# Bunza-DCC-Front-End.net
KiCad netlist of a schematic drawn in EAGLE
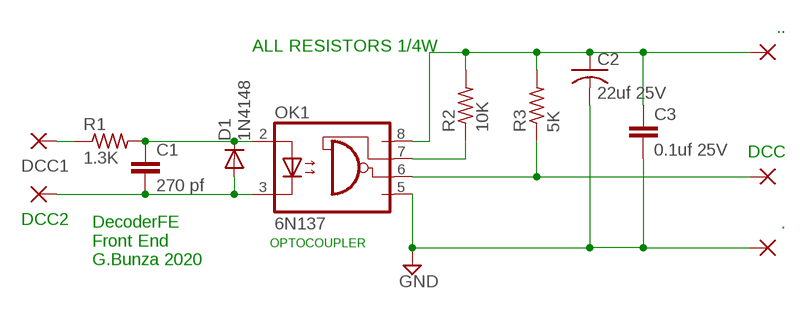
[diagram p0: schematic, sheet 1]

(export (version "E")
  (design (tool "Eeschema 10.0.6"))
  (components
    (comp (ref ".")
      (value "2,15/1,0")
      (footprint "eagle-import:2,15_1,0")
      (libsource (lib "eagle-import") (part "2,15/1,0"))
    )
    (comp (ref "..")
      (value "2,15/1,0")
      (footprint "eagle-import:2,15_1,0")
      (libsource (lib "eagle-import") (part "2,15/1,0"))
    )
    (comp (ref "C1")
      (value "270 pf")
      (footprint "eagle-import:AXIAL-5MM")
      (libsource (lib "eagle-import") (part "CAP_"))
    )
    (comp (ref "C2")
      (value "22uf 25V")
      (footprint "eagle-import:C050-035X075")
      (libsource (lib "eagle-import") (part "C-US050-035X075"))
    )
    (comp (ref "C3")
      (value "0.1uf 25V")
      (footprint "eagle-import:AXIAL-5MM")
      (libsource (lib "eagle-import") (part "CAP_"))
    )
    (comp (ref "D1")
      (value "1N4148")
      (footprint "eagle-import:DO35-7")
      (libsource (lib "eagle-import") (part "1N4148DO35-7"))
    )
    (comp (ref "DCC")
      (value "2,15/1,0")
      (footprint "eagle-import:2,15_1,0")
      (libsource (lib "eagle-import") (part "2,15/1,0"))
    )
    (comp (ref "DCC1")
      (value "2,15/1,0")
      (footprint "eagle-import:2,15_1,0")
      (libsource (lib "eagle-import") (part "2,15/1,0"))
    )
    (comp (ref "DCC2")
      (value "2,15/1,0")
      (footprint "eagle-import:2,15_1,0")
      (libsource (lib "eagle-import") (part "2,15/1,0"))
    )
    (comp (ref "OK1")
      (value "6N137")
      (footprint "eagle-import:DIL08")
      (libsource (lib "eagle-import") (part "6N137"))
    )
    (comp (ref "R1")
      (value "1.3K")
      (footprint "eagle-import:0204_7")
      (libsource (lib "eagle-import") (part "R-US_0204/7"))
    )
    (comp (ref "R2")
      (value "10K")
      (footprint "eagle-import:0204_7")
      (libsource (lib "eagle-import") (part "R-US_0204/7"))
    )
    (comp (ref "R3")
      (value "5K")
      (footprint "eagle-import:0204_7")
      (libsource (lib "eagle-import") (part "R-US_0204/7"))
    )
  )
  (nets
    (net (code "1") (name "GND") (class "Default")
      (node (ref ".") (pin "1") (pinfunction "P_1") (pintype "passive"))
      (node (ref "C2") (pin "2") (pinfunction "2_2") (pintype "passive"))
      (node (ref "C3") (pin "P$2") (pinfunction "2_P$2") (pintype "passive"))
      (node (ref "OK1") (pin "5") (pinfunction "GND_5") (pintype "passive"))
    )
    (net (code "2") (name "Net-(..-P)") (class "Default")
      (node (ref "..") (pin "1") (pinfunction "P_1") (pintype "passive"))
      (node (ref "C2") (pin "1") (pinfunction "1_1") (pintype "passive"))
      (node (ref "C3") (pin "P$1") (pinfunction "1_P$1") (pintype "passive"))
      (node (ref "OK1") (pin "8") (pinfunction "VCC_8") (pintype "passive"))
      (node (ref "R2") (pin "2") (pinfunction "2_2") (pintype "passive"))
      (node (ref "R3") (pin "2") (pinfunction "2_2") (pintype "passive"))
    )
    (net (code "3") (name "Net-(C1-1)") (class "Default")
      (node (ref "C1") (pin "P$1") (pinfunction "1_P$1") (pintype "passive"))
      (node (ref "D1") (pin "C") (pinfunction "C_C") (pintype "passive"))
      (node (ref "OK1") (pin "2") (pinfunction "A_2") (pintype "passive"))
      (node (ref "R1") (pin "2") (pinfunction "2_2") (pintype "passive"))
    )
    (net (code "4") (name "Net-(C1-2)") (class "Default")
      (node (ref "C1") (pin "P$2") (pinfunction "2_P$2") (pintype "passive"))
      (node (ref "D1") (pin "A") (pinfunction "A_A") (pintype "passive"))
      (node (ref "DCC2") (pin "1") (pinfunction "P_1") (pintype "passive"))
      (node (ref "OK1") (pin "3") (pinfunction "C_3") (pintype "passive"))
    )
    (net (code "5") (name "Net-(DCC-P)") (class "Default")
      (node (ref "DCC") (pin "1") (pinfunction "P_1") (pintype "passive"))
      (node (ref "OK1") (pin "6") (pinfunction "VO_6") (pintype "passive"))
      (node (ref "R3") (pin "1") (pinfunction "1_1") (pintype "passive"))
    )
    (net (code "6") (name "Net-(DCC1-P)") (class "Default")
      (node (ref "DCC1") (pin "1") (pinfunction "P_1") (pintype "passive"))
      (node (ref "R1") (pin "1") (pinfunction "1_1") (pintype "passive"))
    )
    (net (code "7") (name "Net-(OK1-VE)") (class "Default")
      (node (ref "OK1") (pin "7") (pinfunction "VE_7") (pintype "passive"))
      (node (ref "R2") (pin "1") (pinfunction "1_1") (pintype "passive"))
    )
  )
)
